# 04_BANK_3_4.net
KiCad netlist of a schematic drawn in Altium Designer
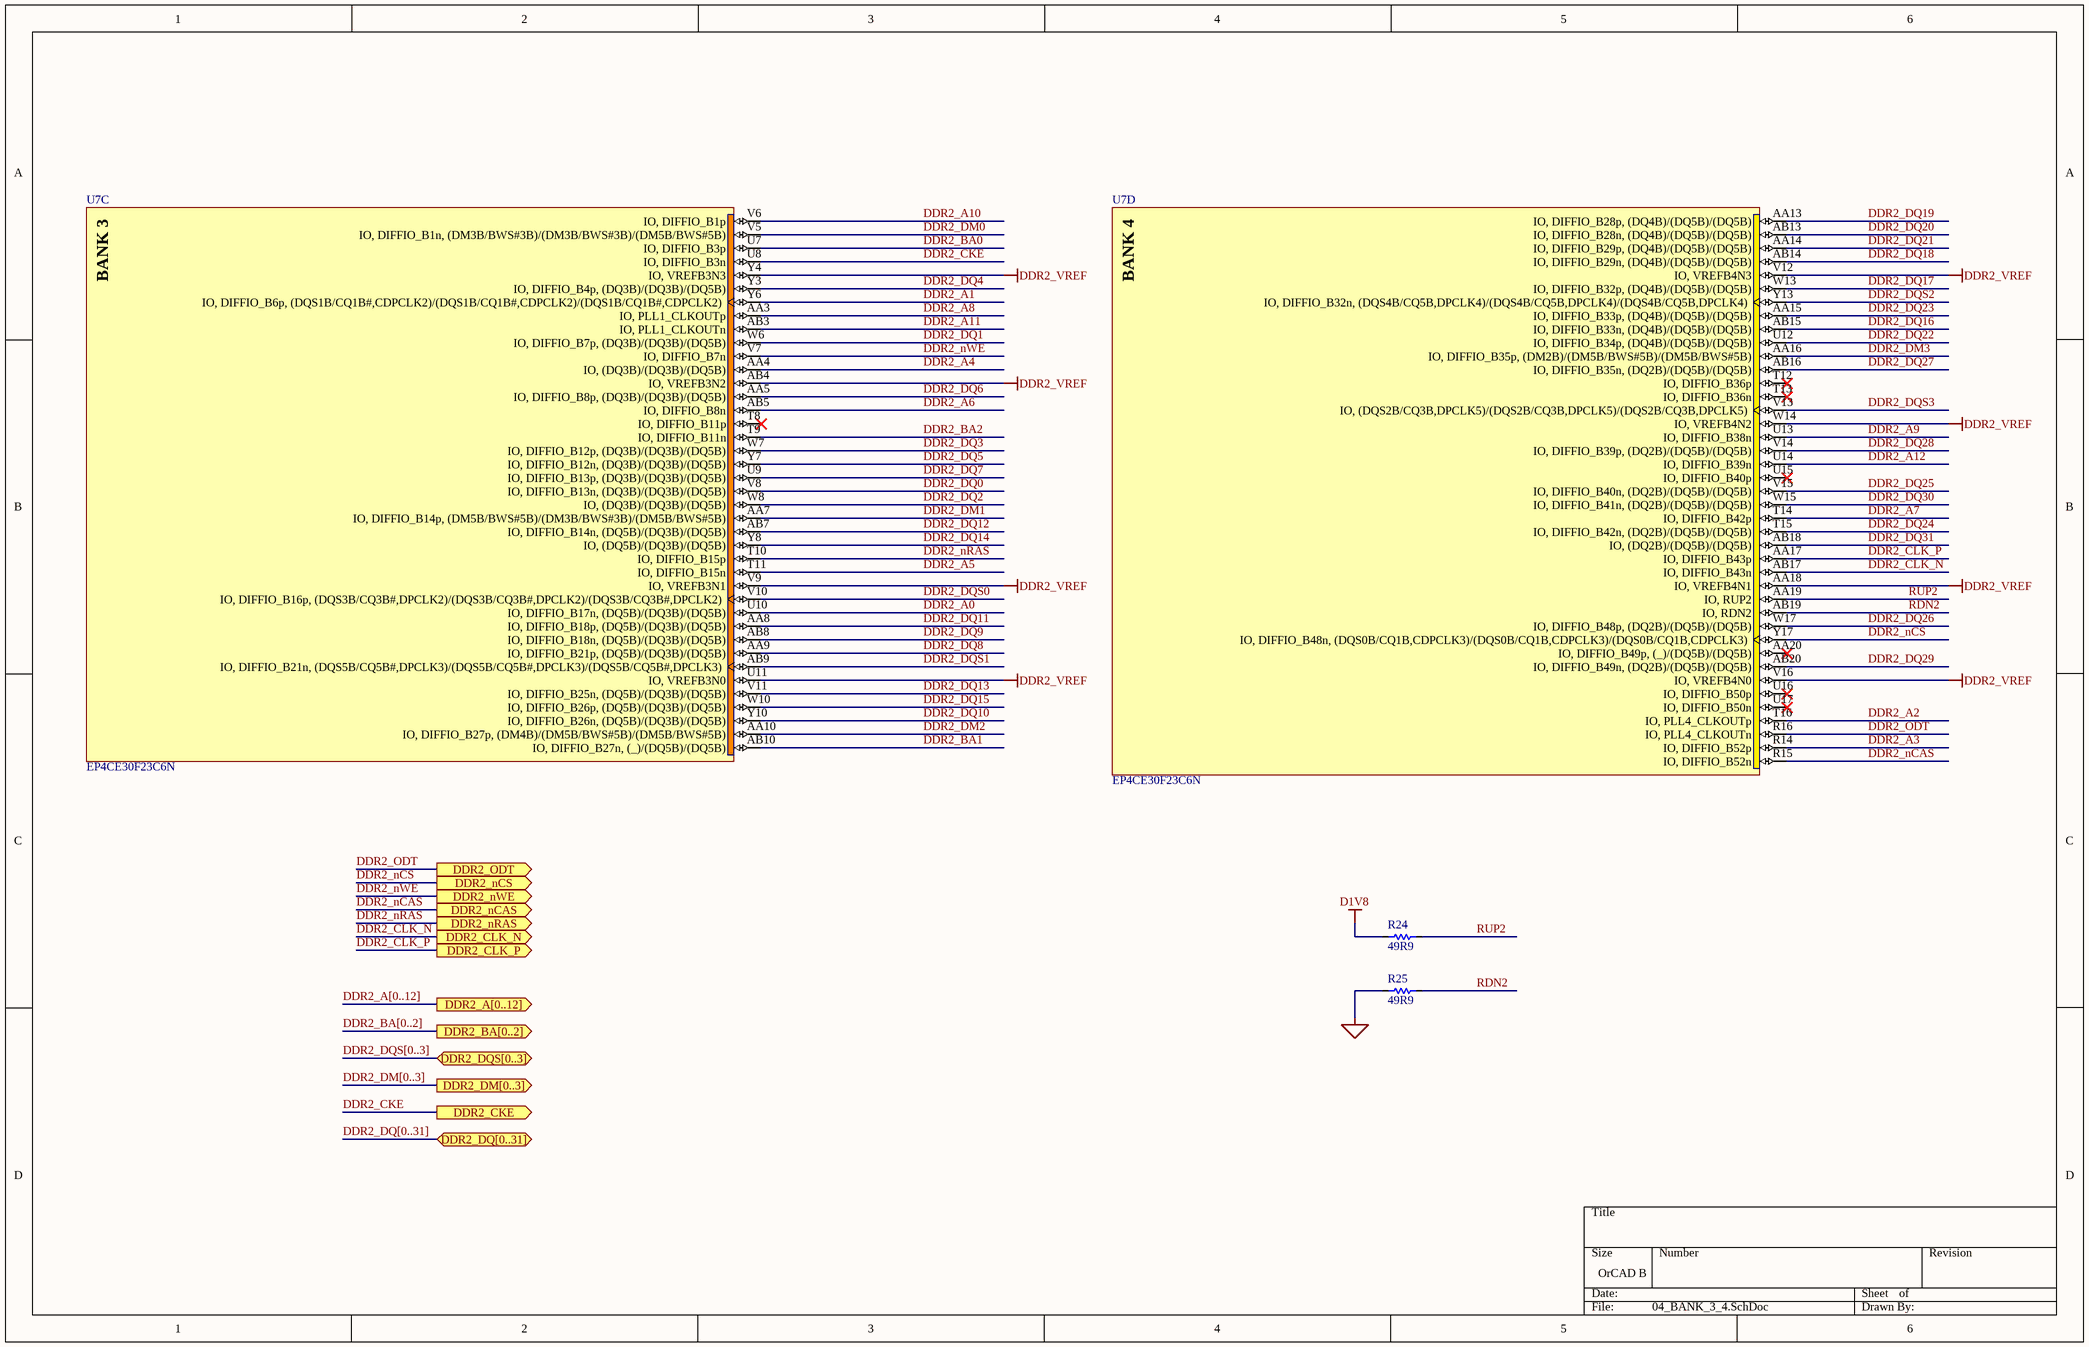
[diagram p0: 04_BANK_3_4.SchDoc]

(export (version "E")
  (design (tool "Eeschema 10.0.6"))
  (components
    (comp (ref "R24")
      (value "49R9")
      (footprint "R0402")
      (description "RES,49R9,1%,1/16W,0402")
      (libsource (lib "R0402") (part "RES0127_1"))
    )
    (comp (ref "R25")
      (value "49R9")
      (footprint "R0402")
      (description "RES,49R9,1%,1/16W,0402")
      (libsource (lib "R0402") (part "RES0127_1"))
    )
    (comp (ref "U7")
      (value "EP4CE30F23C6N")
      (footprint "FBGA484_EP4CE30F23C6N")
      (description "IC,FPGA,28848 LEs,Speed-6,FBGA484")
      (libsource (lib "AD15_Altera_schlib") (part "EP4CE30F23C6N"))
    )
  )
  (nets
    (net (code "1") (name "/DDR2_A0") (class "Default")
      (node (ref "U7") (pin "U10") (pinfunction "IO,_DIFFIO_B17n,_(DQ5B)/(DQ3B)/(DQ5B)_U10") (pintype "bidirectional"))
    )
    (net (code "2") (name "/DDR2_A1") (class "Default")
      (node (ref "U7") (pin "Y6") (pinfunction "IO,_DIFFIO_B6p,_(DQS1B/CQ1B#,CDPCLK2)/(DQS1B/CQ1B#,CDPCLK2)/(DQS1B/CQ1B#,CDPCLK2)_Y6") (pintype "bidirectional"))
    )
    (net (code "3") (name "/DDR2_A2") (class "Default")
      (node (ref "U7") (pin "T16") (pinfunction "IO,_PLL4_CLKOUTp_T16") (pintype "bidirectional"))
    )
    (net (code "4") (name "/DDR2_A3") (class "Default")
      (node (ref "U7") (pin "R14") (pinfunction "IO,_DIFFIO_B52p_R14") (pintype "bidirectional"))
    )
    (net (code "5") (name "/DDR2_A4") (class "Default")
      (node (ref "U7") (pin "AA4") (pinfunction "IO,_(DQ3B)/(DQ3B)/(DQ5B)_AA4") (pintype "bidirectional"))
    )
    (net (code "6") (name "/DDR2_A5") (class "Default")
      (node (ref "U7") (pin "T11") (pinfunction "IO,_DIFFIO_B15n_T11") (pintype "bidirectional"))
    )
    (net (code "7") (name "/DDR2_A6") (class "Default")
      (node (ref "U7") (pin "AB5") (pinfunction "IO,_DIFFIO_B8n_AB5") (pintype "bidirectional"))
    )
    (net (code "8") (name "/DDR2_A7") (class "Default")
      (node (ref "U7") (pin "T14") (pinfunction "IO,_DIFFIO_B42p_T14") (pintype "bidirectional"))
    )
    (net (code "9") (name "/DDR2_A8") (class "Default")
      (node (ref "U7") (pin "AA3") (pinfunction "IO,_PLL1_CLKOUTp_AA3") (pintype "bidirectional"))
    )
    (net (code "10") (name "/DDR2_A9") (class "Default")
      (node (ref "U7") (pin "U13") (pinfunction "IO,_DIFFIO_B38n_U13") (pintype "bidirectional"))
    )
    (net (code "11") (name "/DDR2_A10") (class "Default")
      (node (ref "U7") (pin "V6") (pinfunction "IO,_DIFFIO_B1p_V6") (pintype "bidirectional"))
    )
    (net (code "12") (name "/DDR2_A11") (class "Default")
      (node (ref "U7") (pin "AB3") (pinfunction "IO,_PLL1_CLKOUTn_AB3") (pintype "bidirectional"))
    )
    (net (code "13") (name "/DDR2_A12") (class "Default")
      (node (ref "U7") (pin "U14") (pinfunction "IO,_DIFFIO_B39n_U14") (pintype "bidirectional"))
    )
    (net (code "15") (name "/DDR2_BA0") (class "Default")
      (node (ref "U7") (pin "U7") (pinfunction "IO,_DIFFIO_B3p_U7") (pintype "bidirectional"))
    )
    (net (code "16") (name "/DDR2_BA1") (class "Default")
      (node (ref "U7") (pin "AB10") (pinfunction "IO,_DIFFIO_B27n,_(_)/(DQ5B)/(DQ5B)_AB10") (pintype "bidirectional"))
    )
    (net (code "17") (name "/DDR2_BA2") (class "Default")
      (node (ref "U7") (pin "T9") (pinfunction "IO,_DIFFIO_B11n_T9") (pintype "bidirectional"))
    )
    (net (code "19") (name "/DDR2_CKE") (class "Default")
      (node (ref "U7") (pin "U8") (pinfunction "IO,_DIFFIO_B3n_U8") (pintype "bidirectional"))
    )
    (net (code "20") (name "/DDR2_CLK_N") (class "Default")
      (node (ref "U7") (pin "AB17") (pinfunction "IO,_DIFFIO_B43n_AB17") (pintype "bidirectional"))
    )
    (net (code "21") (name "/DDR2_CLK_P") (class "Default")
      (node (ref "U7") (pin "AA17") (pinfunction "IO,_DIFFIO_B43p_AA17") (pintype "bidirectional"))
    )
    (net (code "22") (name "/DDR2_DM0") (class "Default")
      (node (ref "U7") (pin "V5") (pinfunction "IO,_DIFFIO_B1n,_(DM3B/BWS#3B)/(DM3B/BWS#3B)/(DM5B/BWS#5B)_V5") (pintype "bidirectional"))
    )
    (net (code "23") (name "/DDR2_DM1") (class "Default")
      (node (ref "U7") (pin "AA7") (pinfunction "IO,_DIFFIO_B14p,_(DM5B/BWS#5B)/(DM3B/BWS#3B)/(DM5B/BWS#5B)_AA7") (pintype "bidirectional"))
    )
    (net (code "24") (name "/DDR2_DM2") (class "Default")
      (node (ref "U7") (pin "AA10") (pinfunction "IO,_DIFFIO_B27p,_(DM4B)/(DM5B/BWS#5B)/(DM5B/BWS#5B)_AA10") (pintype "bidirectional"))
    )
    (net (code "25") (name "/DDR2_DM3") (class "Default")
      (node (ref "U7") (pin "AA16") (pinfunction "IO,_DIFFIO_B35p,_(DM2B)/(DM5B/BWS#5B)/(DM5B/BWS#5B)_AA16") (pintype "bidirectional"))
    )
    (net (code "27") (name "/DDR2_DQ0") (class "Default")
      (node (ref "U7") (pin "V8") (pinfunction "IO,_DIFFIO_B13n,_(DQ3B)/(DQ3B)/(DQ5B)_V8") (pintype "bidirectional"))
    )
    (net (code "28") (name "/DDR2_DQ1") (class "Default")
      (node (ref "U7") (pin "W6") (pinfunction "IO,_DIFFIO_B7p,_(DQ3B)/(DQ3B)/(DQ5B)_W6") (pintype "bidirectional"))
    )
    (net (code "29") (name "/DDR2_DQ2") (class "Default")
      (node (ref "U7") (pin "W8") (pinfunction "IO,_(DQ3B)/(DQ3B)/(DQ5B)_W8") (pintype "bidirectional"))
    )
    (net (code "30") (name "/DDR2_DQ3") (class "Default")
      (node (ref "U7") (pin "W7") (pinfunction "IO,_DIFFIO_B12p,_(DQ3B)/(DQ3B)/(DQ5B)_W7") (pintype "bidirectional"))
    )
    (net (code "31") (name "/DDR2_DQ4") (class "Default")
      (node (ref "U7") (pin "Y3") (pinfunction "IO,_DIFFIO_B4p,_(DQ3B)/(DQ3B)/(DQ5B)_Y3") (pintype "bidirectional"))
    )
    (net (code "32") (name "/DDR2_DQ5") (class "Default")
      (node (ref "U7") (pin "Y7") (pinfunction "IO,_DIFFIO_B12n,_(DQ3B)/(DQ3B)/(DQ5B)_Y7") (pintype "bidirectional"))
    )
    (net (code "33") (name "/DDR2_DQ6") (class "Default")
      (node (ref "U7") (pin "AA5") (pinfunction "IO,_DIFFIO_B8p,_(DQ3B)/(DQ3B)/(DQ5B)_AA5") (pintype "bidirectional"))
    )
    (net (code "34") (name "/DDR2_DQ7") (class "Default")
      (node (ref "U7") (pin "U9") (pinfunction "IO,_DIFFIO_B13p,_(DQ3B)/(DQ3B)/(DQ5B)_U9") (pintype "bidirectional"))
    )
    (net (code "35") (name "/DDR2_DQ8") (class "Default")
      (node (ref "U7") (pin "AA9") (pinfunction "IO,_DIFFIO_B21p,_(DQ5B)/(DQ3B)/(DQ5B)_AA9") (pintype "bidirectional"))
    )
    (net (code "36") (name "/DDR2_DQ9") (class "Default")
      (node (ref "U7") (pin "AB8") (pinfunction "IO,_DIFFIO_B18n,_(DQ5B)/(DQ3B)/(DQ5B)_AB8") (pintype "bidirectional"))
    )
    (net (code "37") (name "/DDR2_DQ10") (class "Default")
      (node (ref "U7") (pin "Y10") (pinfunction "IO,_DIFFIO_B26n,_(DQ5B)/(DQ3B)/(DQ5B)_Y10") (pintype "bidirectional"))
    )
    (net (code "38") (name "/DDR2_DQ11") (class "Default")
      (node (ref "U7") (pin "AA8") (pinfunction "IO,_DIFFIO_B18p,_(DQ5B)/(DQ3B)/(DQ5B)_AA8") (pintype "bidirectional"))
    )
    (net (code "39") (name "/DDR2_DQ12") (class "Default")
      (node (ref "U7") (pin "AB7") (pinfunction "IO,_DIFFIO_B14n,_(DQ5B)/(DQ3B)/(DQ5B)_AB7") (pintype "bidirectional"))
    )
    (net (code "40") (name "/DDR2_DQ13") (class "Default")
      (node (ref "U7") (pin "V11") (pinfunction "IO,_DIFFIO_B25n,_(DQ5B)/(DQ3B)/(DQ5B)_V11") (pintype "bidirectional"))
    )
    (net (code "41") (name "/DDR2_DQ14") (class "Default")
      (node (ref "U7") (pin "Y8") (pinfunction "IO,_(DQ5B)/(DQ3B)/(DQ5B)_Y8") (pintype "bidirectional"))
    )
    (net (code "42") (name "/DDR2_DQ15") (class "Default")
      (node (ref "U7") (pin "W10") (pinfunction "IO,_DIFFIO_B26p,_(DQ5B)/(DQ3B)/(DQ5B)_W10") (pintype "bidirectional"))
    )
    (net (code "43") (name "/DDR2_DQ16") (class "Default")
      (node (ref "U7") (pin "AB15") (pinfunction "IO,_DIFFIO_B33n,_(DQ4B)/(DQ5B)/(DQ5B)_AB15") (pintype "bidirectional"))
    )
    (net (code "44") (name "/DDR2_DQ17") (class "Default")
      (node (ref "U7") (pin "W13") (pinfunction "IO,_DIFFIO_B32p,_(DQ4B)/(DQ5B)/(DQ5B)_W13") (pintype "bidirectional"))
    )
    (net (code "45") (name "/DDR2_DQ18") (class "Default")
      (node (ref "U7") (pin "AB14") (pinfunction "IO,_DIFFIO_B29n,_(DQ4B)/(DQ5B)/(DQ5B)_AB14") (pintype "bidirectional"))
    )
    (net (code "46") (name "/DDR2_DQ19") (class "Default")
      (node (ref "U7") (pin "AA13") (pinfunction "IO,_DIFFIO_B28p,_(DQ4B)/(DQ5B)/(DQ5B)_AA13") (pintype "bidirectional"))
    )
    (net (code "47") (name "/DDR2_DQ20") (class "Default")
      (node (ref "U7") (pin "AB13") (pinfunction "IO,_DIFFIO_B28n,_(DQ4B)/(DQ5B)/(DQ5B)_AB13") (pintype "bidirectional"))
    )
    (net (code "48") (name "/DDR2_DQ21") (class "Default")
      (node (ref "U7") (pin "AA14") (pinfunction "IO,_DIFFIO_B29p,_(DQ4B)/(DQ5B)/(DQ5B)_AA14") (pintype "bidirectional"))
    )
    (net (code "49") (name "/DDR2_DQ22") (class "Default")
      (node (ref "U7") (pin "U12") (pinfunction "IO,_DIFFIO_B34p,_(DQ4B)/(DQ5B)/(DQ5B)_U12") (pintype "bidirectional"))
    )
    (net (code "50") (name "/DDR2_DQ23") (class "Default")
      (node (ref "U7") (pin "AA15") (pinfunction "IO,_DIFFIO_B33p,_(DQ4B)/(DQ5B)/(DQ5B)_AA15") (pintype "bidirectional"))
    )
    (net (code "51") (name "/DDR2_DQ24") (class "Default")
      (node (ref "U7") (pin "T15") (pinfunction "IO,_DIFFIO_B42n,_(DQ2B)/(DQ5B)/(DQ5B)_T15") (pintype "bidirectional"))
    )
    (net (code "52") (name "/DDR2_DQ25") (class "Default")
      (node (ref "U7") (pin "V15") (pinfunction "IO,_DIFFIO_B40n,_(DQ2B)/(DQ5B)/(DQ5B)_V15") (pintype "bidirectional"))
    )
    (net (code "53") (name "/DDR2_DQ26") (class "Default")
      (node (ref "U7") (pin "W17") (pinfunction "IO,_DIFFIO_B48p,_(DQ2B)/(DQ5B)/(DQ5B)_W17") (pintype "bidirectional"))
    )
    (net (code "54") (name "/DDR2_DQ27") (class "Default")
      (node (ref "U7") (pin "AB16") (pinfunction "IO,_DIFFIO_B35n,_(DQ2B)/(DQ5B)/(DQ5B)_AB16") (pintype "bidirectional"))
    )
    (net (code "55") (name "/DDR2_DQ28") (class "Default")
      (node (ref "U7") (pin "V14") (pinfunction "IO,_DIFFIO_B39p,_(DQ2B)/(DQ5B)/(DQ5B)_V14") (pintype "bidirectional"))
    )
    (net (code "56") (name "/DDR2_DQ29") (class "Default")
      (node (ref "U7") (pin "AB20") (pinfunction "IO,_DIFFIO_B49n,_(DQ2B)/(DQ5B)/(DQ5B)_AB20") (pintype "bidirectional"))
    )
    (net (code "57") (name "/DDR2_DQ30") (class "Default")
      (node (ref "U7") (pin "W15") (pinfunction "IO,_DIFFIO_B41n,_(DQ2B)/(DQ5B)/(DQ5B)_W15") (pintype "bidirectional"))
    )
    (net (code "58") (name "/DDR2_DQ31") (class "Default")
      (node (ref "U7") (pin "AB18") (pinfunction "IO,_(DQ2B)/(DQ5B)/(DQ5B)_AB18") (pintype "bidirectional"))
    )
    (net (code "59") (name "/DDR2_DQS0") (class "Default")
      (node (ref "U7") (pin "V10") (pinfunction "IO,_DIFFIO_B16p,_(DQS3B/CQ3B#,DPCLK2)/(DQS3B/CQ3B#,DPCLK2)/(DQS3B/CQ3B#,DPCLK2)_V10") (pintype "bidirectional"))
    )
    (net (code "60") (name "/DDR2_DQS1") (class "Default")
      (node (ref "U7") (pin "AB9") (pinfunction "IO,_DIFFIO_B21n,_(DQS5B/CQ5B#,DPCLK3)/(DQS5B/CQ5B#,DPCLK3)/(DQS5B/CQ5B#,DPCLK3)_AB9") (pintype "bidirectional"))
    )
    (net (code "61") (name "/DDR2_DQS2") (class "Default")
      (node (ref "U7") (pin "Y13") (pinfunction "IO,_DIFFIO_B32n,_(DQS4B/CQ5B,DPCLK4)/(DQS4B/CQ5B,DPCLK4)/(DQS4B/CQ5B,DPCLK4)_Y13") (pintype "bidirectional"))
    )
    (net (code "62") (name "/DDR2_DQS3") (class "Default")
      (node (ref "U7") (pin "V13") (pinfunction "IO,_(DQS2B/CQ3B,DPCLK5)/(DQS2B/CQ3B,DPCLK5)/(DQS2B/CQ3B,DPCLK5)_V13") (pintype "bidirectional"))
    )
    (net (code "65") (name "/DDR2_ODT") (class "Default")
      (node (ref "U7") (pin "R16") (pinfunction "IO,_PLL4_CLKOUTn_R16") (pintype "bidirectional"))
    )
    (net (code "66") (name "/DDR2_nCAS") (class "Default")
      (node (ref "U7") (pin "R15") (pinfunction "IO,_DIFFIO_B52n_R15") (pintype "bidirectional"))
    )
    (net (code "67") (name "/DDR2_nCS") (class "Default")
      (node (ref "U7") (pin "Y17") (pinfunction "IO,_DIFFIO_B48n,_(DQS0B/CQ1B,CDPCLK3)/(DQS0B/CQ1B,CDPCLK3)/(DQS0B/CQ1B,CDPCLK3)_Y17") (pintype "bidirectional"))
    )
    (net (code "68") (name "/DDR2_nRAS") (class "Default")
      (node (ref "U7") (pin "T10") (pinfunction "IO,_DIFFIO_B15p_T10") (pintype "bidirectional"))
    )
    (net (code "69") (name "/DDR2_nWE") (class "Default")
      (node (ref "U7") (pin "V7") (pinfunction "IO,_DIFFIO_B7n_V7") (pintype "bidirectional"))
    )
    (net (code "70") (name "/RDN2") (class "Default")
      (node (ref "R25") (pin "2") (pinfunction "2_2") (pintype "passive"))
      (node (ref "U7") (pin "AB19") (pinfunction "IO,_RDN2_AB19") (pintype "bidirectional"))
    )
    (net (code "71") (name "/RUP2") (class "Default")
      (node (ref "R24") (pin "2") (pinfunction "2_2") (pintype "passive"))
      (node (ref "U7") (pin "AA19") (pinfunction "IO,_RUP2_AA19") (pintype "bidirectional"))
    )
    (net (code "72") (name "D1V8") (class "Default")
      (node (ref "R24") (pin "1") (pinfunction "0_1") (pintype "passive"))
    )
    (net (code "73") (name "DDR2_VREF") (class "Default")
      (node (ref "U7") (pin "AA18") (pinfunction "IO,_VREFB4N1_AA18") (pintype "bidirectional"))
      (node (ref "U7") (pin "AB4") (pinfunction "IO,_VREFB3N2_AB4") (pintype "bidirectional"))
      (node (ref "U7") (pin "U11") (pinfunction "IO,_VREFB3N0_U11") (pintype "bidirectional"))
      (node (ref "U7") (pin "V12") (pinfunction "IO,_VREFB4N3_V12") (pintype "bidirectional"))
      (node (ref "U7") (pin "V16") (pinfunction "IO,_VREFB4N0_V16") (pintype "bidirectional"))
      (node (ref "U7") (pin "V9") (pinfunction "IO,_VREFB3N1_V9") (pintype "bidirectional"))
      (node (ref "U7") (pin "W14") (pinfunction "IO,_VREFB4N2_W14") (pintype "bidirectional"))
      (node (ref "U7") (pin "Y4") (pinfunction "IO,_VREFB3N3_Y4") (pintype "bidirectional"))
    )
    (net (code "74") (name "GND") (class "Default")
      (node (ref "R25") (pin "1") (pinfunction "0_1") (pintype "passive"))
    )
    (net (code "75") (name "unconnected-(U7C-IO,_DIFFIO_B11p-PadT8)") (class "Default")
      (node (ref "U7") (pin "T8") (pinfunction "IO,_DIFFIO_B11p_T8") (pintype "bidirectional+no_connect"))
    )
    (net (code "76") (name "unconnected-(U7D-IO,_DIFFIO_B36n-PadT13)") (class "Default")
      (node (ref "U7") (pin "T13") (pinfunction "IO,_DIFFIO_B36n_T13") (pintype "bidirectional+no_connect"))
    )
    (net (code "77") (name "unconnected-(U7D-IO,_DIFFIO_B36p-PadT12)") (class "Default")
      (node (ref "U7") (pin "T12") (pinfunction "IO,_DIFFIO_B36p_T12") (pintype "bidirectional+no_connect"))
    )
    (net (code "78") (name "unconnected-(U7D-IO,_DIFFIO_B40p-PadU15)") (class "Default")
      (node (ref "U7") (pin "U15") (pinfunction "IO,_DIFFIO_B40p_U15") (pintype "bidirectional+no_connect"))
    )
    (net (code "79") (name "unconnected-(U7D-IO,_DIFFIO_B49p,_(_){slash}(DQ5B){slash}(DQ5B)-PadAA20)") (class "Default")
      (node (ref "U7") (pin "AA20") (pinfunction "IO,_DIFFIO_B49p,_(_)/(DQ5B)/(DQ5B)_AA20") (pintype "bidirectional+no_connect"))
    )
    (net (code "80") (name "unconnected-(U7D-IO,_DIFFIO_B50n-PadU17)") (class "Default")
      (node (ref "U7") (pin "U17") (pinfunction "IO,_DIFFIO_B50n_U17") (pintype "bidirectional+no_connect"))
    )
    (net (code "81") (name "unconnected-(U7D-IO,_DIFFIO_B50p-PadU16)") (class "Default")
      (node (ref "U7") (pin "U16") (pinfunction "IO,_DIFFIO_B50p_U16") (pintype "bidirectional+no_connect"))
    )
  )
)
